# Wikipilot.net
KiCad netlist of a schematic drawn in Altium Designer
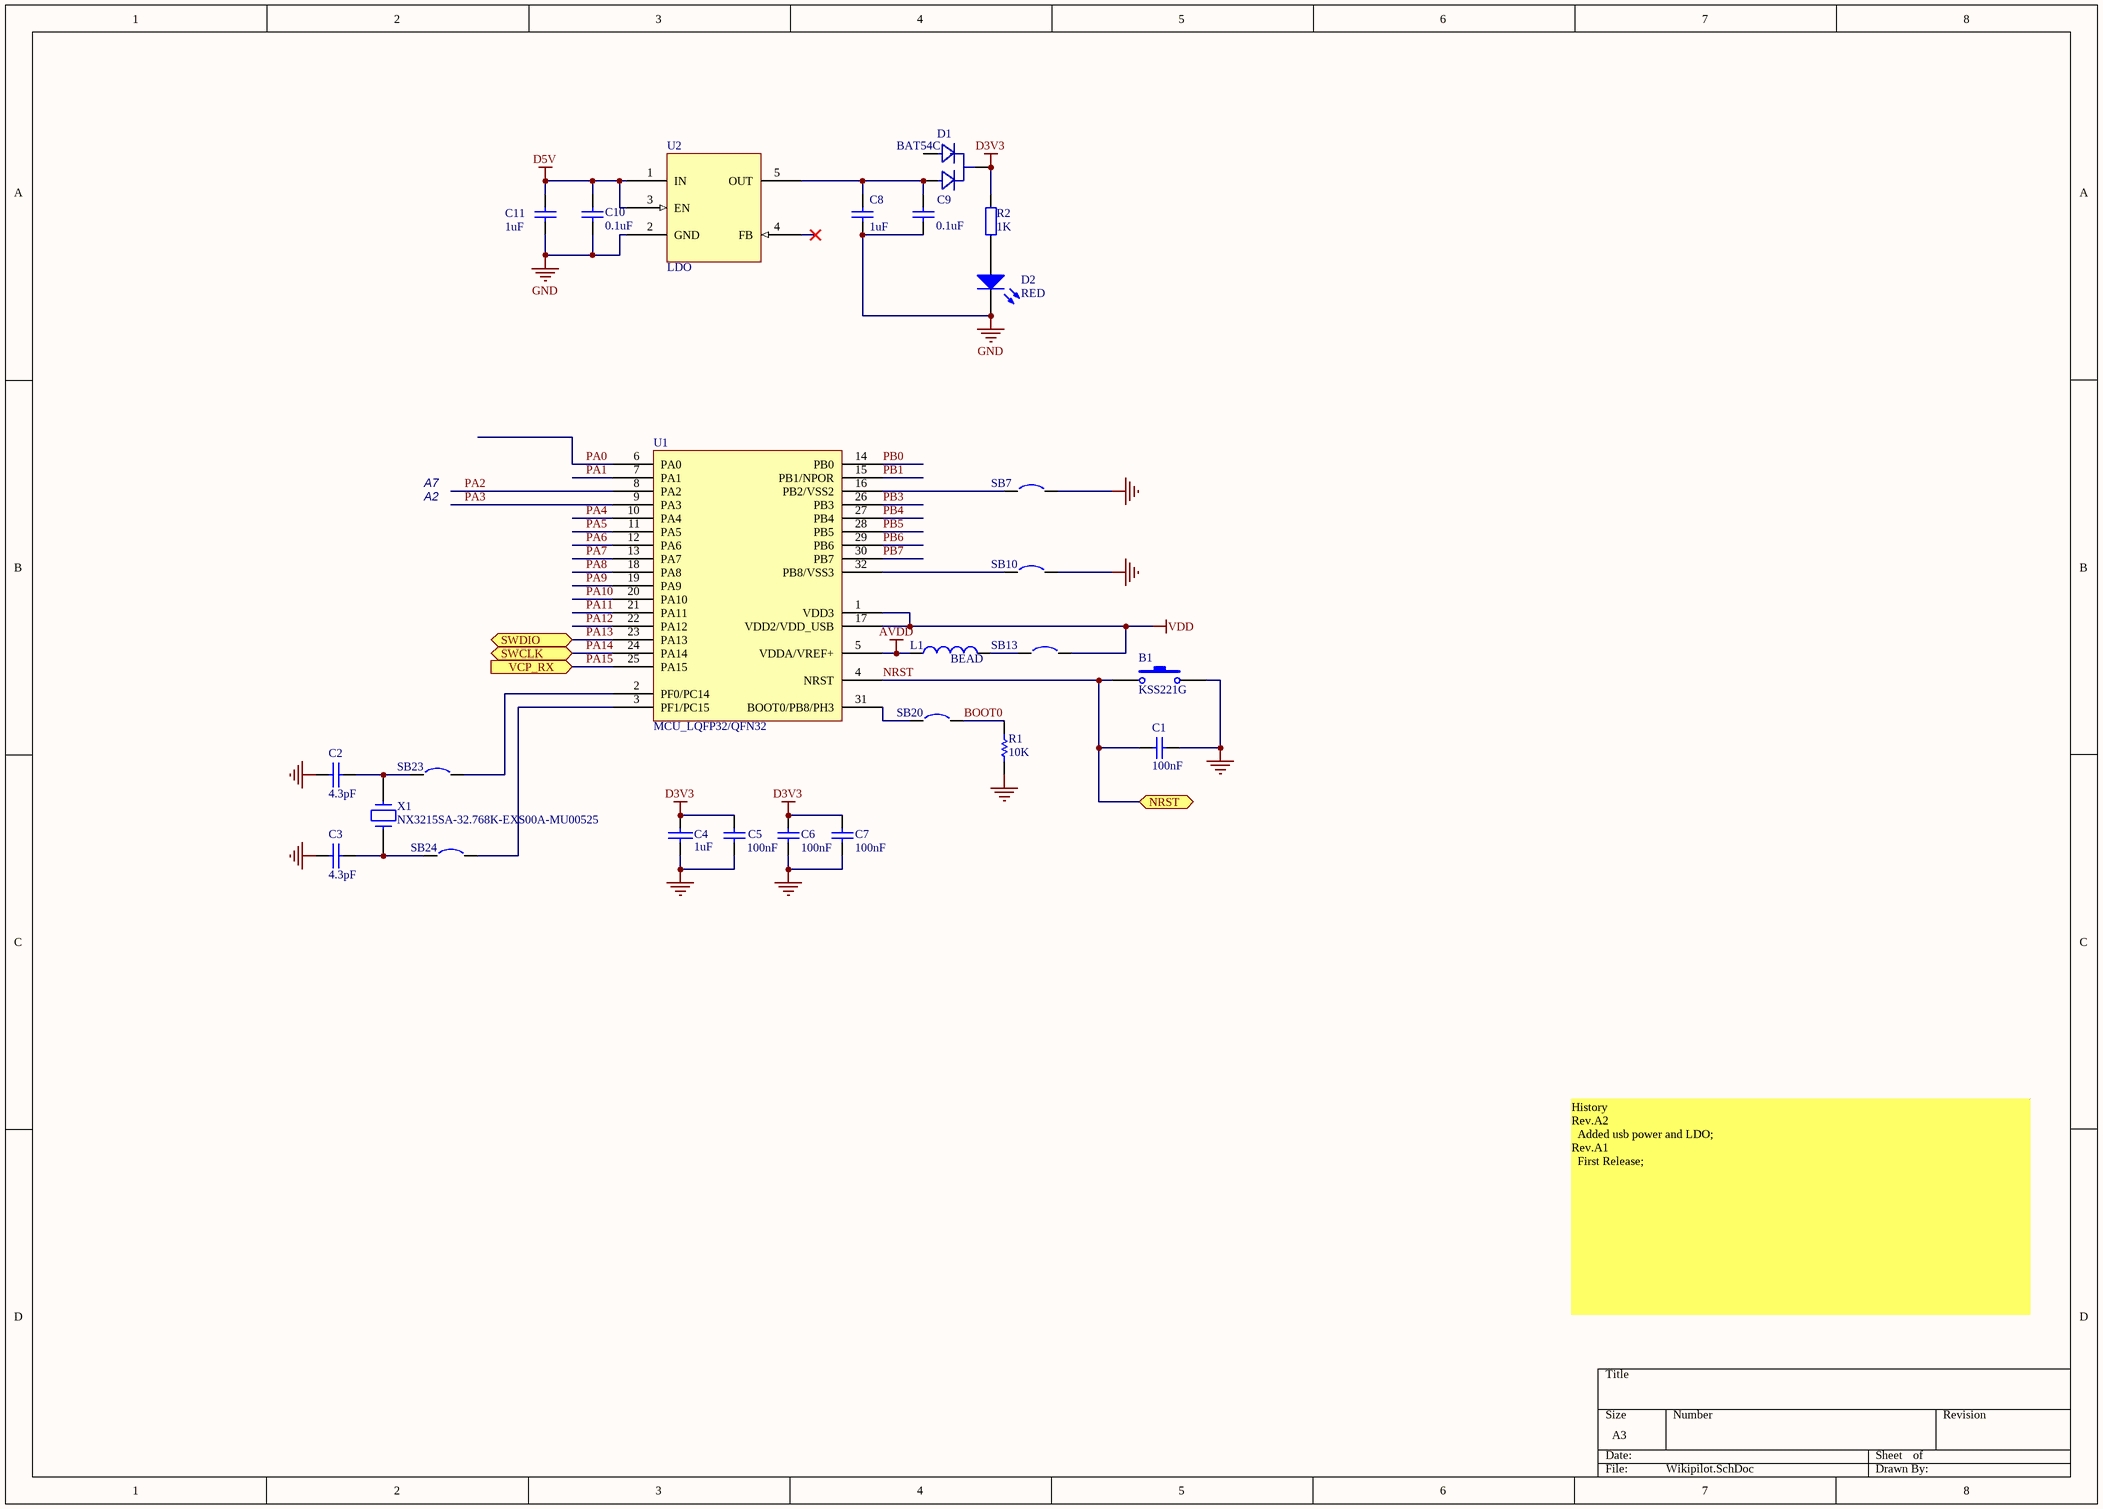
[diagram p0: Wikipilot.SchDoc]

(export (version "E")
  (design (tool "Eeschema 10.0.6"))
  (components
    (comp (ref "B1")
      (value "KSS221G")
      (footprint "SW2_5R6_5R5x3R1")
      (description "Switch")
      (fields (field (name "PUBLISHER") "Altium Limited"))
      (libsource (lib "Miscellaneous Devices") (part "SW-PB"))
    )
    (comp (ref "C1")
      (value "100nF")
      (footprint "0603C")
      (description "Capacitor")
      (fields (field (name "PUBLISHER") "Altium Limited"))
      (libsource (lib "Miscellaneous Devices") (part "CAP"))
    )
    (comp (ref "C2")
      (value "4.3pF")
      (footprint "0603C")
      (description "Capacitor")
      (libsource (lib "*") (part "CAP"))
    )
    (comp (ref "C3")
      (value "4.3pF")
      (footprint "0603C")
      (description "Capacitor")
      (libsource (lib "*") (part "CAP"))
    )
    (comp (ref "C4")
      (value "1uF")
      (footprint "0603M")
      (description "Capacitor")
      (libsource (lib "*") (part "CAP"))
    )
    (comp (ref "C5")
      (value "100nF")
      (footprint "0603M")
      (description "Capacitor")
      (fields (field (name "PUBLISHER") "Altium Limited"))
      (libsource (lib "Miscellaneous Devices") (part "Cap"))
    )
    (comp (ref "C6")
      (value "100nF")
      (footprint "0603M")
      (description "Capacitor")
      (fields (field (name "PUBLISHER") "Altium Limited"))
      (libsource (lib "Miscellaneous Devices") (part "Cap"))
    )
    (comp (ref "C7")
      (value "100nF")
      (footprint "0603M")
      (description "Capacitor")
      (fields (field (name "PUBLISHER") "Altium Limited"))
      (libsource (lib "Miscellaneous Devices") (part "Cap"))
    )
    (comp (ref "C8")
      (value "1uF")
      (footprint "0603M")
      (description "Capacitor")
      (libsource (lib "Studio") (part "Cap"))
    )
    (comp (ref "C9")
      (value "0.1uF")
      (footprint "0603M")
      (description "Capacitor")
      (libsource (lib "Studio") (part "Cap"))
    )
    (comp (ref "C10")
      (value "0.1uF")
      (footprint "0603M")
      (description "Capacitor")
      (libsource (lib "Studio") (part "Cap"))
    )
    (comp (ref "C11")
      (value "1uF")
      (footprint "0603M")
      (description "Capacitor")
      (libsource (lib "Studio") (part "Cap"))
    )
    (comp (ref "D1")
      (value "BAT54C")
      (footprint "BAT54C")
      (description "DOUBLE SHOTTKEY DIODES")
      (libsource (lib "Misc") (part "BAT54C"))
    )
    (comp (ref "D2")
      (value "RED")
      (footprint "0603pn")
      (description "Typical INFRARED GaAs LED")
      (fields (field (name "PUBLISHER") "Altium Limited"))
      (libsource (lib "Miscellaneous Devices") (part "LED0"))
    )
    (comp (ref "L1")
      (value "BEAD")
      (footprint "0603L")
      (description "Inductor")
      (fields (field (name "PUBLISHER") "Altium Limited"))
      (libsource (lib "Miscellaneous Devices") (part "Inductor"))
    )
    (comp (ref "R1")
      (value "10K")
      (footprint "0603R")
      (description "Resistor")
      (fields (field (name "PUBLISHER") "Altium Limited"))
      (libsource (lib "Miscellaneous Devices") (part "res1"))
    )
    (comp (ref "R2")
      (value "1K")
      (footprint "0603M")
      (description "Resistor")
      (fields (field (name "PUBLISHER") "Altium Limited"))
      (libsource (lib "Miscellaneous Devices") (part "Res2"))
    )
    (comp (ref "SB7")
      (value "Circuit Breaker (close)")
      (footprint "SB_0603")
      (description "Circuit Breaker")
      (fields (field (name "PUBLISHER") "Altium Limited"))
      (libsource (lib "MCD_TOOLS") (part "Circuit Breaker"))
    )
    (comp (ref "SB10")
      (value "Circuit Breaker (close)")
      (footprint "SB_0603")
      (description "Circuit Breaker")
      (fields (field (name "PUBLISHER") "Altium Limited"))
      (libsource (lib "MCD_TOOLS") (part "Circuit Breaker"))
    )
    (comp (ref "SB13")
      (value "Circuit Breaker (close)")
      (footprint "SB_0603")
      (description "Circuit Breaker")
      (fields (field (name "PUBLISHER") "Altium Limited"))
      (libsource (lib "MCD_TOOLS") (part "Circuit Breaker"))
    )
    (comp (ref "SB20")
      (value "Circuit Breaker (close)")
      (footprint "SB_0603")
      (description "Circuit Breaker")
      (fields (field (name "PUBLISHER") "Altium Limited"))
      (libsource (lib "MCD_TOOLS") (part "Circuit Breaker"))
    )
    (comp (ref "SB23")
      (value "Circuit Breaker")
      (footprint "SB_0603")
      (fields (field (name "PUBLISHER") "Altium Limited"))
      (libsource (lib "MCD_TOOLS") (part "Circuit Breaker"))
    )
    (comp (ref "SB24")
      (value "Circuit Breaker")
      (footprint "SB_0603")
      (fields (field (name "PUBLISHER") "Altium Limited"))
      (libsource (lib "MCD_TOOLS") (part "Circuit Breaker"))
    )
    (comp (ref "U1")
      (value "MCU_LQFP32/QFN32")
      (footprint "LQFP32_0R5_7x7")
      (libsource (lib "MB1180") (part "MCU_LQFP32"))
    )
    (comp (ref "U2")
      (value "LDO")
      (footprint "SOT23-5L")
      (description "General LDO SOT23-5")
      (libsource (lib "Power") (part "LDO-SOT23-5"))
    )
    (comp (ref "X1")
      (value "NX3215SA-32.768K-EXS00A-MU00525")
      (footprint "XTAL_2SM_3R2X1R5")
      (description "Crystal")
      (libsource (lib "MB1167") (part "CRYSTAL_32K"))
    )
  )
  (nets
    (net (code "1") (name "/BOOT0") (class "Default")
      (node (ref "R1") (pin "1") (pinfunction "1_1") (pintype "passive"))
      (node (ref "SB20") (pin "2") (pinfunction "2_2") (pintype "passive"))
    )
    (net (code "2") (name "/NRST") (class "Default")
      (node (ref "B1") (pin "1") (pinfunction "1_1") (pintype "passive"))
      (node (ref "C1") (pin "2") (pinfunction "2_2") (pintype "passive"))
      (node (ref "U1") (pin "4") (pinfunction "NRST_4") (pintype "passive"))
    )
    (net (code "3") (name "/PA0") (class "Default")
      (node (ref "U1") (pin "6") (pinfunction "PA0_6") (pintype "passive"))
    )
    (net (code "4") (name "/PA1") (class "Default")
      (node (ref "U1") (pin "7") (pinfunction "PA1_7") (pintype "passive"))
    )
    (net (code "5") (name "/PA2") (class "Default")
      (node (ref "U1") (pin "8") (pinfunction "PA2_8") (pintype "passive"))
    )
    (net (code "6") (name "/PA3") (class "Default")
      (node (ref "U1") (pin "9") (pinfunction "PA3_9") (pintype "passive"))
    )
    (net (code "7") (name "/PA4") (class "Default")
      (node (ref "U1") (pin "10") (pinfunction "PA4_10") (pintype "passive"))
    )
    (net (code "8") (name "/PA5") (class "Default")
      (node (ref "U1") (pin "11") (pinfunction "PA5_11") (pintype "passive"))
    )
    (net (code "9") (name "/PA6") (class "Default")
      (node (ref "U1") (pin "12") (pinfunction "PA6_12") (pintype "passive"))
    )
    (net (code "10") (name "/PA7") (class "Default")
      (node (ref "U1") (pin "13") (pinfunction "PA7_13") (pintype "passive"))
    )
    (net (code "11") (name "/PA8") (class "Default")
      (node (ref "U1") (pin "18") (pinfunction "PA8_18") (pintype "passive"))
    )
    (net (code "12") (name "/PA9") (class "Default")
      (node (ref "U1") (pin "19") (pinfunction "PA9_19") (pintype "passive"))
    )
    (net (code "13") (name "/PA10") (class "Default")
      (node (ref "U1") (pin "20") (pinfunction "PA10_20") (pintype "passive"))
    )
    (net (code "14") (name "/PA11") (class "Default")
      (node (ref "U1") (pin "21") (pinfunction "PA11_21") (pintype "passive"))
    )
    (net (code "15") (name "/PA12") (class "Default")
      (node (ref "U1") (pin "22") (pinfunction "PA12_22") (pintype "passive"))
    )
    (net (code "16") (name "/PA13") (class "Default")
      (node (ref "U1") (pin "23") (pinfunction "PA13_23") (pintype "passive"))
    )
    (net (code "17") (name "/PA14") (class "Default")
      (node (ref "U1") (pin "24") (pinfunction "PA14_24") (pintype "passive"))
    )
    (net (code "18") (name "/PA15") (class "Default")
      (node (ref "U1") (pin "25") (pinfunction "PA15_25") (pintype "passive"))
    )
    (net (code "19") (name "/PB0") (class "Default")
      (node (ref "U1") (pin "14") (pinfunction "PB0_14") (pintype "passive"))
    )
    (net (code "20") (name "/PB1") (class "Default")
      (node (ref "U1") (pin "15") (pinfunction "PB1/NPOR_15") (pintype "passive"))
    )
    (net (code "21") (name "/PB3") (class "Default")
      (node (ref "U1") (pin "26") (pinfunction "PB3_26") (pintype "passive"))
    )
    (net (code "22") (name "/PB4") (class "Default")
      (node (ref "U1") (pin "27") (pinfunction "PB4_27") (pintype "passive"))
    )
    (net (code "23") (name "/PB5") (class "Default")
      (node (ref "U1") (pin "28") (pinfunction "PB5_28") (pintype "passive"))
    )
    (net (code "24") (name "/PB6") (class "Default")
      (node (ref "U1") (pin "29") (pinfunction "PB6_29") (pintype "passive"))
    )
    (net (code "25") (name "/PB7") (class "Default")
      (node (ref "U1") (pin "30") (pinfunction "PB7_30") (pintype "passive"))
    )
    (net (code "26") (name "AVDD") (class "Default")
      (node (ref "L1") (pin "1") (pinfunction "1_1") (pintype "passive"))
      (node (ref "U1") (pin "5") (pinfunction "VDDA/VREF+_5") (pintype "passive"))
    )
    (net (code "27") (name "D3V3") (class "Default")
      (node (ref "C4") (pin "1") (pinfunction "1_1") (pintype "passive"))
      (node (ref "C5") (pin "1") (pinfunction "1_1") (pintype "passive"))
      (node (ref "C6") (pin "1") (pinfunction "1_1") (pintype "passive"))
      (node (ref "C7") (pin "1") (pinfunction "1_1") (pintype "passive"))
      (node (ref "D1") (pin "3") (pinfunction "3_3") (pintype "passive"))
      (node (ref "R2") (pin "2") (pinfunction "2_2") (pintype "passive"))
    )
    (net (code "28") (name "D5V") (class "Default")
      (node (ref "C10") (pin "2") (pinfunction "2_2") (pintype "passive"))
      (node (ref "C11") (pin "2") (pinfunction "2_2") (pintype "passive"))
      (node (ref "U2") (pin "1") (pinfunction "IN_1") (pintype "power_in"))
      (node (ref "U2") (pin "3") (pinfunction "EN_3") (pintype "input"))
    )
    (net (code "29") (name "GND") (class "Default")
      (node (ref "B1") (pin "2") (pinfunction "2_2") (pintype "passive"))
      (node (ref "C1") (pin "1") (pinfunction "1_1") (pintype "passive"))
      (node (ref "C10") (pin "1") (pinfunction "1_1") (pintype "passive"))
      (node (ref "C11") (pin "1") (pinfunction "1_1") (pintype "passive"))
      (node (ref "C2") (pin "2") (pinfunction "2_2") (pintype "passive"))
      (node (ref "C3") (pin "2") (pinfunction "2_2") (pintype "passive"))
      (node (ref "C4") (pin "2") (pinfunction "2_2") (pintype "passive"))
      (node (ref "C5") (pin "2") (pinfunction "2_2") (pintype "passive"))
      (node (ref "C6") (pin "2") (pinfunction "2_2") (pintype "passive"))
      (node (ref "C7") (pin "2") (pinfunction "2_2") (pintype "passive"))
      (node (ref "C8") (pin "1") (pinfunction "1_1") (pintype "passive"))
      (node (ref "C9") (pin "1") (pinfunction "1_1") (pintype "passive"))
      (node (ref "D2") (pin "2") (pinfunction "K_2") (pintype "passive"))
      (node (ref "R1") (pin "2") (pinfunction "2_2") (pintype "passive"))
      (node (ref "SB10") (pin "2") (pinfunction "2_2") (pintype "passive"))
      (node (ref "SB7") (pin "2") (pinfunction "2_2") (pintype "passive"))
      (node (ref "U2") (pin "2") (pinfunction "GND_2") (pintype "power_in"))
    )
    (net (code "30") (name "Net-(C2-Pad1)") (class "Default")
      (node (ref "C2") (pin "1") (pinfunction "1_1") (pintype "passive"))
      (node (ref "SB23") (pin "1") (pinfunction "1_1") (pintype "passive"))
      (node (ref "X1") (pin "1") (pinfunction "1_1") (pintype "passive"))
    )
    (net (code "31") (name "Net-(C3-Pad1)") (class "Default")
      (node (ref "C3") (pin "1") (pinfunction "1_1") (pintype "passive"))
      (node (ref "SB24") (pin "1") (pinfunction "1_1") (pintype "passive"))
      (node (ref "X1") (pin "2") (pinfunction "2_2") (pintype "passive"))
    )
    (net (code "32") (name "Net-(D2-A)") (class "Default")
      (node (ref "D2") (pin "1") (pinfunction "A_1") (pintype "passive"))
      (node (ref "R2") (pin "1") (pinfunction "1_1") (pintype "passive"))
    )
    (net (code "33") (name "Net-(L1-Pad2)") (class "Default")
      (node (ref "L1") (pin "2") (pinfunction "2_2") (pintype "passive"))
      (node (ref "SB13") (pin "1") (pinfunction "1_1") (pintype "passive"))
    )
    (net (code "34") (name "Net-(U1-BOOT0{slash}PB8{slash}PH3)") (class "Default")
      (node (ref "SB20") (pin "1") (pinfunction "1_1") (pintype "passive"))
      (node (ref "U1") (pin "31") (pinfunction "BOOT0/PB8/PH3_31") (pintype "passive"))
    )
    (net (code "35") (name "Net-(U1-PB2{slash}VSS2)") (class "Default")
      (node (ref "SB7") (pin "1") (pinfunction "1_1") (pintype "passive"))
      (node (ref "U1") (pin "16") (pinfunction "PB2/VSS2_16") (pintype "passive"))
    )
    (net (code "36") (name "Net-(U1-PB8{slash}VSS3)") (class "Default")
      (node (ref "SB10") (pin "1") (pinfunction "1_1") (pintype "passive"))
      (node (ref "U1") (pin "32") (pinfunction "PB8/VSS3_32") (pintype "passive"))
    )
    (net (code "37") (name "Net-(U1-PF0{slash}PC14)") (class "Default")
      (node (ref "SB23") (pin "2") (pinfunction "2_2") (pintype "passive"))
      (node (ref "U1") (pin "2") (pinfunction "PF0/PC14_2") (pintype "passive"))
    )
    (net (code "38") (name "Net-(U1-PF1{slash}PC15)") (class "Default")
      (node (ref "SB24") (pin "2") (pinfunction "2_2") (pintype "passive"))
      (node (ref "U1") (pin "3") (pinfunction "PF1/PC15_3") (pintype "passive"))
    )
    (net (code "39") (name "Net-(U2-OUT)") (class "Default")
      (node (ref "C8") (pin "2") (pinfunction "2_2") (pintype "passive"))
      (node (ref "C9") (pin "2") (pinfunction "2_2") (pintype "passive"))
      (node (ref "D1") (pin "2") (pintype "passive"))
      (node (ref "U2") (pin "5") (pinfunction "OUT_5") (pintype "power_in"))
    )
    (net (code "40") (name "VDD") (class "Default")
      (node (ref "SB13") (pin "2") (pinfunction "2_2") (pintype "passive"))
      (node (ref "U1") (pin "1") (pinfunction "VDD3_1") (pintype "passive"))
      (node (ref "U1") (pin "17") (pinfunction "VDD2/VDD_USB_17") (pintype "passive"))
    )
    (net (code "41") (name "unconnected-(D1-Pad1)") (class "Default")
      (node (ref "D1") (pin "1") (pintype "passive"))
    )
    (net (code "42") (name "unconnected-(U2-FB-Pad4)") (class "Default")
      (node (ref "U2") (pin "4") (pinfunction "FB_4") (pintype "input+no_connect"))
    )
  )
)
